# mend.net
KiCad netlist of a schematic drawn in EAGLE
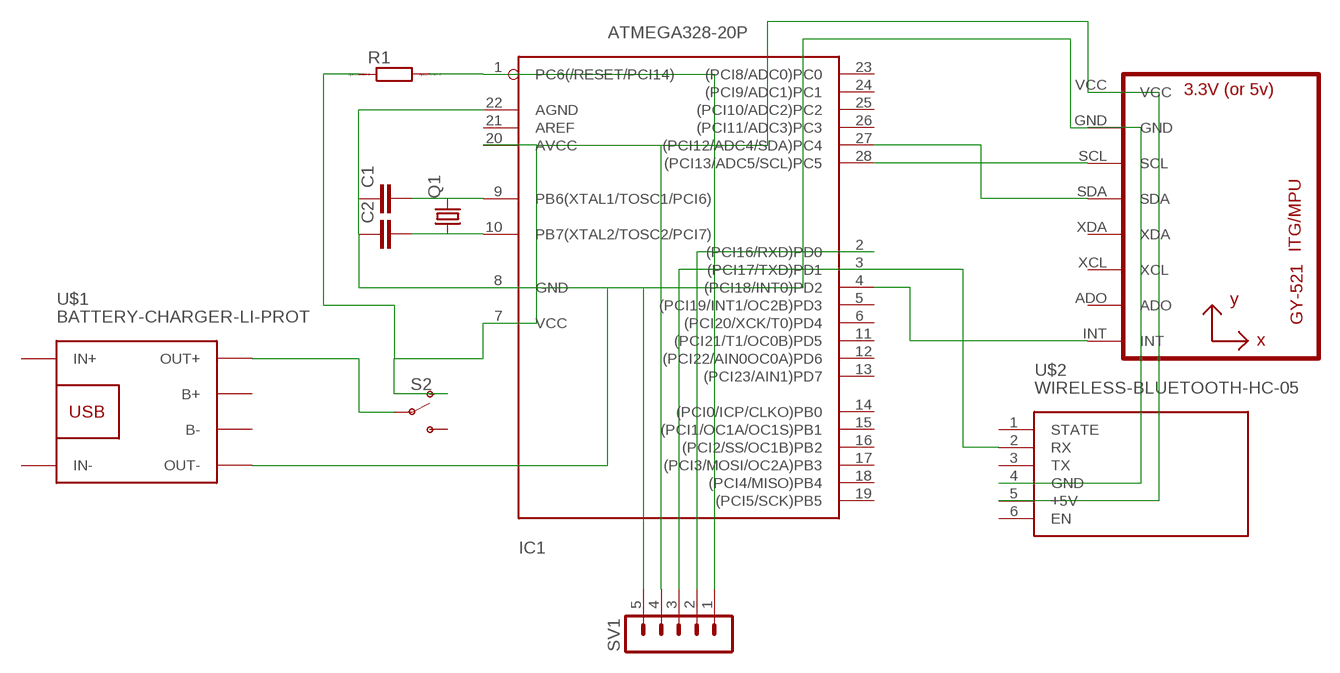
[diagram p0: schematic, sheet 1]

(export (version "E")
  (design (tool "Eeschema 10.0.6"))
  (components
    (comp (ref "C1")
      (value "C2.5/2")
      (footprint "eagle-import:C2.5-2")
      (libsource (lib "eagle-import") (part "C2.5/2"))
    )
    (comp (ref "C2")
      (value "C2.5/2")
      (footprint "eagle-import:C2.5-2")
      (libsource (lib "eagle-import") (part "C2.5/2"))
    )
    (comp (ref "IC1")
      (value "ATMEGA328-20P")
      (footprint "eagle-import:DIL28-3")
      (libsource (lib "eagle-import") (part "ATMEGA328P-20"))
    )
    (comp (ref "Q1")
      (value "CRYSTALHC49S")
      (footprint "eagle-import:HC49_S")
      (libsource (lib "eagle-import") (part "CRYSTALHC49S"))
    )
    (comp (ref "R1")
      (value "R0204/7")
      (footprint "eagle-import:0204_7")
      (libsource (lib "eagle-import") (part "R0204/7"))
    )
    (comp (ref "S2")
      (value "SWITCH-SPDT-PTH-8.6X4.3MM-LOCK")
      (footprint "eagle-import:SWITCH_SPDT_8.6X4.3MM_LOCK")
      (libsource (lib "eagle-import") (part "SWITCH-SPDT-PTH-8.6X4.3MM-LOCK"))
    )
    (comp (ref "SV1")
      (value "MA05-1")
      (footprint "eagle-import:MA05-1")
      (libsource (lib "eagle-import") (part "MA05-1"))
    )
    (comp (ref "U$1")
      (value "BATTERY-CHARGER-LI-PROT")
      (footprint "eagle-import:BATTERY-CHARGER-LI-PROT")
      (libsource (lib "eagle-import") (part "BATTERY-CHARGER-LI-PROT"))
    )
    (comp (ref "U$2")
      (value "WIRELESS-BLUETOOTH-HC-05")
      (footprint "eagle-import:WIRELESS-BLUETOOTH-HC-05")
      (libsource (lib "eagle-import") (part "WIRELESS-BLUETOOTH-HC-05"))
    )
    (comp (ref "U1")
      (value "GY-521MPU6050")
      (footprint "eagle-import:GY-521")
      (libsource (lib "eagle-import") (part "GY-521MPU6050"))
    )
  )
  (nets
    (net (code "1") (name "Net-(IC1-(PCI12{slash}ADC4{slash}SDA)PC4)") (class "Default")
      (node (ref "IC1") (pin "27") (pinfunction "(PCI12/ADC4/SDA)PC4_27") (pintype "bidirectional"))
      (node (ref "U1") (pin "SDA") (pinfunction "SDA_SDA") (pintype "bidirectional"))
    )
    (net (code "2") (name "Net-(IC1-(PCI13{slash}ADC5{slash}SCL)PC5)") (class "Default")
      (node (ref "IC1") (pin "28") (pinfunction "(PCI13/ADC5/SCL)PC5_28") (pintype "bidirectional"))
      (node (ref "U1") (pin "SCL") (pinfunction "SCL_SCL") (pintype "bidirectional"))
    )
    (net (code "3") (name "Net-(IC1-(PCI16{slash}RXD)PD0)") (class "Default")
      (node (ref "IC1") (pin "2") (pinfunction "(PCI16/RXD)PD0_2") (pintype "bidirectional"))
      (node (ref "SV1") (pin "2") (pinfunction "2_2") (pintype "passive"))
    )
    (net (code "4") (name "Net-(IC1-(PCI17{slash}TXD)PD1)") (class "Default")
      (node (ref "IC1") (pin "3") (pinfunction "(PCI17/TXD)PD1_3") (pintype "bidirectional"))
      (node (ref "SV1") (pin "3") (pinfunction "3_3") (pintype "passive"))
      (node (ref "U$2") (pin "2") (pinfunction "RX_2") (pintype "bidirectional"))
    )
    (net (code "5") (name "Net-(IC1-(PCI18{slash}INT0)PD2)") (class "Default")
      (node (ref "IC1") (pin "4") (pinfunction "(PCI18/INT0)PD2_4") (pintype "bidirectional"))
      (node (ref "U1") (pin "INT") (pinfunction "INT_INT") (pintype "bidirectional"))
    )
    (net (code "6") (name "Net-(IC1-AGND)") (class "Default")
      (node (ref "C1") (pin "1") (pinfunction "1_1") (pintype "passive"))
      (node (ref "C2") (pin "1") (pinfunction "1_1") (pintype "passive"))
      (node (ref "IC1") (pin "22") (pinfunction "AGND_22") (pintype "bidirectional"))
      (node (ref "IC1") (pin "8") (pinfunction "GND_8") (pintype "bidirectional"))
      (node (ref "SV1") (pin "5") (pinfunction "5_5") (pintype "passive"))
      (node (ref "U$1") (pin "OUT-") (pinfunction "OUT-_OUT-") (pintype "bidirectional"))
      (node (ref "U$2") (pin "4") (pinfunction "GND_4") (pintype "power_in"))
      (node (ref "U1") (pin "GND") (pinfunction "GND_GND") (pintype "bidirectional"))
    )
    (net (code "7") (name "Net-(IC1-AVCC)") (class "Default")
      (node (ref "IC1") (pin "20") (pinfunction "AVCC_20") (pintype "bidirectional"))
      (node (ref "IC1") (pin "7") (pinfunction "VCC_7") (pintype "bidirectional"))
      (node (ref "R1") (pin "1") (pinfunction "1_1") (pintype "passive"))
      (node (ref "S2") (pin "1") (pinfunction "O_1") (pintype "passive"))
      (node (ref "SV1") (pin "4") (pinfunction "4_4") (pintype "passive"))
      (node (ref "U$2") (pin "5") (pinfunction "+5V_5") (pintype "power_in"))
      (node (ref "U1") (pin "VCC") (pinfunction "VCC_VCC") (pintype "bidirectional"))
    )
    (net (code "8") (name "Net-(IC1-PB6(XTAL1{slash}TOSC1{slash}PCI6))") (class "Default")
      (node (ref "C1") (pin "2") (pinfunction "2_2") (pintype "passive"))
      (node (ref "IC1") (pin "9") (pinfunction "PB6(XTAL1/TOSC1/PCI6)_9") (pintype "bidirectional"))
      (node (ref "Q1") (pin "2") (pinfunction "2_2") (pintype "passive"))
    )
    (net (code "9") (name "Net-(IC1-PB7(XTAL2{slash}TOSC2{slash}PCI7))") (class "Default")
      (node (ref "C2") (pin "2") (pinfunction "2_2") (pintype "passive"))
      (node (ref "IC1") (pin "10") (pinfunction "PB7(XTAL2/TOSC2/PCI7)_10") (pintype "bidirectional"))
      (node (ref "Q1") (pin "1") (pinfunction "1_1") (pintype "passive"))
    )
    (net (code "10") (name "Net-(IC1-PC6({slash}RESET{slash}PCI14))") (class "Default")
      (node (ref "IC1") (pin "1") (pinfunction "PC6(/RESET/PCI14)_1") (pintype "bidirectional"))
      (node (ref "R1") (pin "2") (pinfunction "2_2") (pintype "passive"))
      (node (ref "SV1") (pin "1") (pinfunction "1_1") (pintype "passive"))
    )
    (net (code "11") (name "Net-(S2-P)") (class "Default")
      (node (ref "S2") (pin "2") (pinfunction "P_2") (pintype "passive"))
      (node (ref "U$1") (pin "OUT+") (pinfunction "OUT+_OUT+") (pintype "bidirectional"))
    )
    (net (code "12") (name "unconnected-(IC1-(PCI0{slash}ICP{slash}CLKO)PB0-Pad14)") (class "Default")
      (node (ref "IC1") (pin "14") (pinfunction "(PCI0/ICP/CLKO)PB0_14") (pintype "bidirectional"))
    )
    (net (code "13") (name "unconnected-(IC1-(PCI1{slash}OC1A{slash}OC1S)PB1-Pad15)") (class "Default")
      (node (ref "IC1") (pin "15") (pinfunction "(PCI1/OC1A/OC1S)PB1_15") (pintype "bidirectional"))
    )
    (net (code "14") (name "unconnected-(IC1-(PCI2{slash}SS{slash}OC1B)PB2-Pad16)") (class "Default")
      (node (ref "IC1") (pin "16") (pinfunction "(PCI2/SS/OC1B)PB2_16") (pintype "bidirectional"))
    )
    (net (code "15") (name "unconnected-(IC1-(PCI3{slash}MOSI{slash}OC2A)PB3-Pad17)") (class "Default")
      (node (ref "IC1") (pin "17") (pinfunction "(PCI3/MOSI/OC2A)PB3_17") (pintype "bidirectional"))
    )
    (net (code "16") (name "unconnected-(IC1-(PCI4{slash}MISO)PB4-Pad18)") (class "Default")
      (node (ref "IC1") (pin "18") (pinfunction "(PCI4/MISO)PB4_18") (pintype "bidirectional"))
    )
    (net (code "17") (name "unconnected-(IC1-(PCI5{slash}SCK)PB5-Pad19)") (class "Default")
      (node (ref "IC1") (pin "19") (pinfunction "(PCI5/SCK)PB5_19") (pintype "bidirectional"))
    )
    (net (code "18") (name "unconnected-(IC1-(PCI8{slash}ADC0)PC0-Pad23)") (class "Default")
      (node (ref "IC1") (pin "23") (pinfunction "(PCI8/ADC0)PC0_23") (pintype "bidirectional"))
    )
    (net (code "19") (name "unconnected-(IC1-(PCI9{slash}ADC1)PC1-Pad24)") (class "Default")
      (node (ref "IC1") (pin "24") (pinfunction "(PCI9/ADC1)PC1_24") (pintype "bidirectional"))
    )
    (net (code "20") (name "unconnected-(IC1-(PCI10{slash}ADC2)PC2-Pad25)") (class "Default")
      (node (ref "IC1") (pin "25") (pinfunction "(PCI10/ADC2)PC2_25") (pintype "bidirectional"))
    )
    (net (code "21") (name "unconnected-(IC1-(PCI11{slash}ADC3)PC3-Pad26)") (class "Default")
      (node (ref "IC1") (pin "26") (pinfunction "(PCI11/ADC3)PC3_26") (pintype "bidirectional"))
    )
    (net (code "22") (name "unconnected-(IC1-(PCI19{slash}INT1{slash}OC2B)PD3-Pad5)") (class "Default")
      (node (ref "IC1") (pin "5") (pinfunction "(PCI19/INT1/OC2B)PD3_5") (pintype "bidirectional"))
    )
    (net (code "23") (name "unconnected-(IC1-(PCI20{slash}XCK{slash}T0)PD4-Pad6)") (class "Default")
      (node (ref "IC1") (pin "6") (pinfunction "(PCI20/XCK/T0)PD4_6") (pintype "bidirectional"))
    )
    (net (code "24") (name "unconnected-(IC1-(PCI21{slash}T1{slash}OC0B)PD5-Pad11)") (class "Default")
      (node (ref "IC1") (pin "11") (pinfunction "(PCI21/T1/OC0B)PD5_11") (pintype "bidirectional"))
    )
    (net (code "25") (name "unconnected-(IC1-(PCI22{slash}AIN0OC0A)PD6-Pad12)") (class "Default")
      (node (ref "IC1") (pin "12") (pinfunction "(PCI22/AIN0OC0A)PD6_12") (pintype "bidirectional"))
    )
    (net (code "26") (name "unconnected-(IC1-(PCI23{slash}AIN1)PD7-Pad13)") (class "Default")
      (node (ref "IC1") (pin "13") (pinfunction "(PCI23/AIN1)PD7_13") (pintype "bidirectional"))
    )
    (net (code "27") (name "unconnected-(IC1-AREF-Pad21)") (class "Default")
      (node (ref "IC1") (pin "21") (pinfunction "AREF_21") (pintype "bidirectional"))
    )
    (net (code "28") (name "unconnected-(S2-S-Pad3)") (class "Default")
      (node (ref "S2") (pin "3") (pinfunction "S_3") (pintype "passive"))
    )
    (net (code "29") (name "unconnected-(U$1-PadB+)") (class "Default")
      (node (ref "U$1") (pin "B+") (pinfunction "B+_B+") (pintype "bidirectional"))
    )
    (net (code "30") (name "unconnected-(U$1-PadB-)") (class "Default")
      (node (ref "U$1") (pin "B-") (pinfunction "B-_B-") (pintype "bidirectional"))
    )
    (net (code "31") (name "unconnected-(U$1-PadIN+)") (class "Default")
      (node (ref "U$1") (pin "IN+") (pinfunction "IN+_IN+") (pintype "bidirectional"))
    )
    (net (code "32") (name "unconnected-(U$1-PadIN-)") (class "Default")
      (node (ref "U$1") (pin "IN-") (pinfunction "IN-_IN-") (pintype "bidirectional"))
    )
    (net (code "33") (name "unconnected-(U$2-EN-Pad6)") (class "Default")
      (node (ref "U$2") (pin "6") (pinfunction "EN_6") (pintype "bidirectional"))
    )
    (net (code "34") (name "unconnected-(U$2-STATE-Pad1)") (class "Default")
      (node (ref "U$2") (pin "1") (pinfunction "STATE_1") (pintype "bidirectional"))
    )
    (net (code "35") (name "unconnected-(U$2-TX-Pad3)") (class "Default")
      (node (ref "U$2") (pin "3") (pinfunction "TX_3") (pintype "bidirectional"))
    )
    (net (code "36") (name "unconnected-(U1-PadADO)") (class "Default")
      (node (ref "U1") (pin "ADO") (pinfunction "ADO_ADO") (pintype "bidirectional"))
    )
    (net (code "37") (name "unconnected-(U1-PadXCL)") (class "Default")
      (node (ref "U1") (pin "XCL") (pinfunction "XCL_XCL") (pintype "bidirectional"))
    )
    (net (code "38") (name "unconnected-(U1-PadXDA)") (class "Default")
      (node (ref "U1") (pin "XDA") (pinfunction "XDA_XDA") (pintype "bidirectional"))
    )
  )
)
